# Shift_Registers.net
KiCad netlist of a schematic drawn in Altium Designer
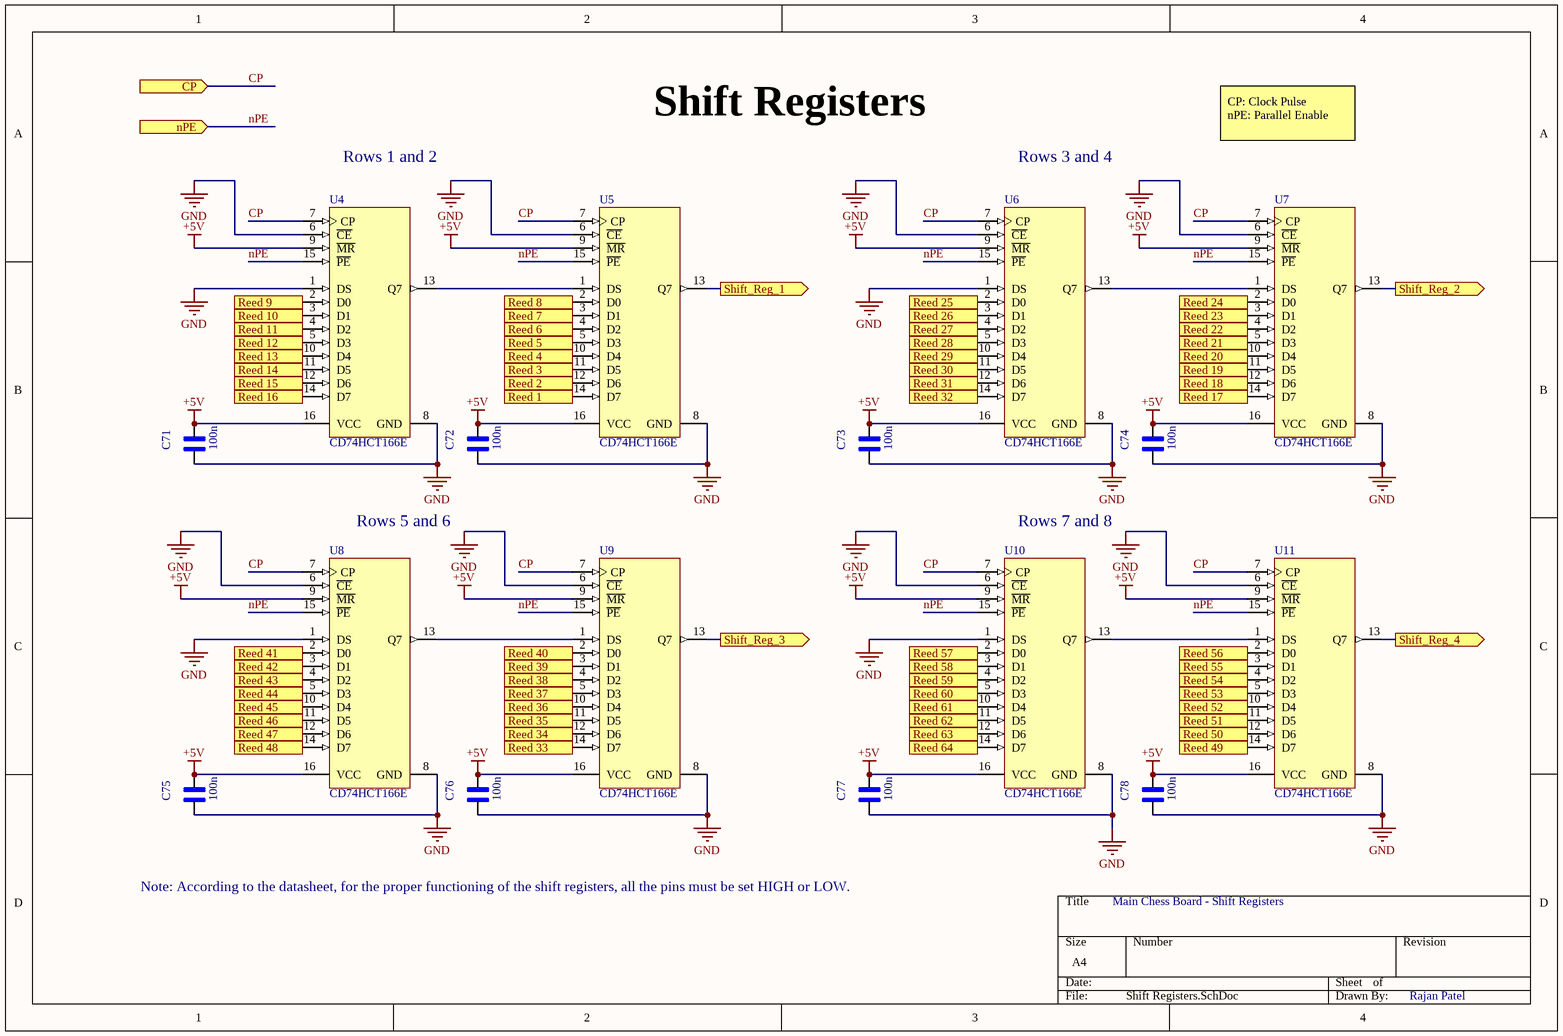
[diagram p0: Shift Registers.SchDoc]

(export (version "E")
  (design (tool "Eeschema 10.0.6"))
  (components
    (comp (ref "C71")
      (value "100n")
      (footprint "CAP 0805")
      (libsource (lib "MiniChessBoardSchLib") (part "CAP 0805"))
    )
    (comp (ref "C72")
      (value "100n")
      (footprint "CAP 0805")
      (libsource (lib "MiniChessBoardSchLib") (part "CAP 0805"))
    )
    (comp (ref "C73")
      (value "100n")
      (footprint "CAP 0805")
      (libsource (lib "MiniChessBoardSchLib") (part "CAP 0805"))
    )
    (comp (ref "C74")
      (value "100n")
      (footprint "CAP 0805")
      (libsource (lib "MiniChessBoardSchLib") (part "CAP 0805"))
    )
    (comp (ref "C75")
      (value "100n")
      (footprint "CAP 0805")
      (libsource (lib "MiniChessBoardSchLib") (part "CAP 0805"))
    )
    (comp (ref "C76")
      (value "100n")
      (footprint "CAP 0805")
      (libsource (lib "MiniChessBoardSchLib") (part "CAP 0805"))
    )
    (comp (ref "C77")
      (value "100n")
      (footprint "CAP 0805")
      (libsource (lib "MiniChessBoardSchLib") (part "CAP 0805"))
    )
    (comp (ref "C78")
      (value "100n")
      (footprint "CAP 0805")
      (libsource (lib "MiniChessBoardSchLib") (part "CAP 0805"))
    )
    (comp (ref "U4")
      (value "CD74HCT166E")
      (footprint "N0016A")
      (description "High Speed CMOS Logic 8-Bit Parallel-In/Serial-Out Shift Register, N0016A, TUBE")
      (fields
        (field (name "MANUFACTURER") "Texas Instruments")
        (field (name "GENERIC PART NUMBER") "CD74HCT166")
      )
      (libsource (lib "Altium Content Vault") (part "TI-CDX4HCX166-16"))
    )
    (comp (ref "U5")
      (value "CD74HCT166E")
      (footprint "N0016A")
      (description "High Speed CMOS Logic 8-Bit Parallel-In/Serial-Out Shift Register, N0016A, TUBE")
      (fields
        (field (name "MANUFACTURER") "Texas Instruments")
        (field (name "GENERIC PART NUMBER") "CD74HCT166")
      )
      (libsource (lib "Altium Content Vault") (part "TI-CDX4HCX166-16"))
    )
    (comp (ref "U6")
      (value "CD74HCT166E")
      (footprint "N0016A")
      (description "High Speed CMOS Logic 8-Bit Parallel-In/Serial-Out Shift Register, N0016A, TUBE")
      (fields
        (field (name "MANUFACTURER") "Texas Instruments")
        (field (name "GENERIC PART NUMBER") "CD74HCT166")
      )
      (libsource (lib "Altium Content Vault") (part "TI-CDX4HCX166-16"))
    )
    (comp (ref "U7")
      (value "CD74HCT166E")
      (footprint "N0016A")
      (description "High Speed CMOS Logic 8-Bit Parallel-In/Serial-Out Shift Register, N0016A, TUBE")
      (fields
        (field (name "MANUFACTURER") "Texas Instruments")
        (field (name "GENERIC PART NUMBER") "CD74HCT166")
      )
      (libsource (lib "Altium Content Vault") (part "TI-CDX4HCX166-16"))
    )
    (comp (ref "U8")
      (value "CD74HCT166E")
      (footprint "N0016A")
      (description "High Speed CMOS Logic 8-Bit Parallel-In/Serial-Out Shift Register, N0016A, TUBE")
      (fields
        (field (name "MANUFACTURER") "Texas Instruments")
        (field (name "GENERIC PART NUMBER") "CD74HCT166")
      )
      (libsource (lib "Altium Content Vault") (part "TI-CDX4HCX166-16"))
    )
    (comp (ref "U9")
      (value "CD74HCT166E")
      (footprint "N0016A")
      (description "High Speed CMOS Logic 8-Bit Parallel-In/Serial-Out Shift Register, N0016A, TUBE")
      (fields
        (field (name "MANUFACTURER") "Texas Instruments")
        (field (name "GENERIC PART NUMBER") "CD74HCT166")
      )
      (libsource (lib "Altium Content Vault") (part "TI-CDX4HCX166-16"))
    )
    (comp (ref "U10")
      (value "CD74HCT166E")
      (footprint "N0016A")
      (description "High Speed CMOS Logic 8-Bit Parallel-In/Serial-Out Shift Register, N0016A, TUBE")
      (fields
        (field (name "MANUFACTURER") "Texas Instruments")
        (field (name "GENERIC PART NUMBER") "CD74HCT166")
      )
      (libsource (lib "Altium Content Vault") (part "TI-CDX4HCX166-16"))
    )
    (comp (ref "U11")
      (value "CD74HCT166E")
      (footprint "N0016A")
      (description "High Speed CMOS Logic 8-Bit Parallel-In/Serial-Out Shift Register, N0016A, TUBE")
      (fields
        (field (name "MANUFACTURER") "Texas Instruments")
        (field (name "GENERIC PART NUMBER") "CD74HCT166")
      )
      (libsource (lib "Altium Content Vault") (part "TI-CDX4HCX166-16"))
    )
  )
  (nets
    (net (code "1") (name "+5V") (class "Default")
      (node (ref "C71") (pin "2") (pinfunction "2_2") (pintype "passive"))
      (node (ref "C72") (pin "2") (pinfunction "2_2") (pintype "passive"))
      (node (ref "C73") (pin "2") (pinfunction "2_2") (pintype "passive"))
      (node (ref "C74") (pin "2") (pinfunction "2_2") (pintype "passive"))
      (node (ref "C75") (pin "2") (pinfunction "2_2") (pintype "passive"))
      (node (ref "C76") (pin "2") (pinfunction "2_2") (pintype "passive"))
      (node (ref "C77") (pin "2") (pinfunction "2_2") (pintype "passive"))
      (node (ref "C78") (pin "2") (pinfunction "2_2") (pintype "passive"))
      (node (ref "U10") (pin "16") (pinfunction "VCC_16") (pintype "power_in"))
      (node (ref "U10") (pin "9") (pinfunction "~{MR}_9") (pintype "input"))
      (node (ref "U11") (pin "16") (pinfunction "VCC_16") (pintype "power_in"))
      (node (ref "U11") (pin "9") (pinfunction "~{MR}_9") (pintype "input"))
      (node (ref "U4") (pin "16") (pinfunction "VCC_16") (pintype "power_in"))
      (node (ref "U4") (pin "9") (pinfunction "~{MR}_9") (pintype "input"))
      (node (ref "U5") (pin "16") (pinfunction "VCC_16") (pintype "power_in"))
      (node (ref "U5") (pin "9") (pinfunction "~{MR}_9") (pintype "input"))
      (node (ref "U6") (pin "16") (pinfunction "VCC_16") (pintype "power_in"))
      (node (ref "U6") (pin "9") (pinfunction "~{MR}_9") (pintype "input"))
      (node (ref "U7") (pin "16") (pinfunction "VCC_16") (pintype "power_in"))
      (node (ref "U7") (pin "9") (pinfunction "~{MR}_9") (pintype "input"))
      (node (ref "U8") (pin "16") (pinfunction "VCC_16") (pintype "power_in"))
      (node (ref "U8") (pin "9") (pinfunction "~{MR}_9") (pintype "input"))
      (node (ref "U9") (pin "16") (pinfunction "VCC_16") (pintype "power_in"))
      (node (ref "U9") (pin "9") (pinfunction "~{MR}_9") (pintype "input"))
    )
    (net (code "2") (name "/CP") (class "Default")
      (node (ref "U10") (pin "7") (pinfunction "CP_7") (pintype "input"))
      (node (ref "U11") (pin "7") (pinfunction "CP_7") (pintype "input"))
      (node (ref "U4") (pin "7") (pinfunction "CP_7") (pintype "input"))
      (node (ref "U5") (pin "7") (pinfunction "CP_7") (pintype "input"))
      (node (ref "U6") (pin "7") (pinfunction "CP_7") (pintype "input"))
      (node (ref "U7") (pin "7") (pinfunction "CP_7") (pintype "input"))
      (node (ref "U8") (pin "7") (pinfunction "CP_7") (pintype "input"))
      (node (ref "U9") (pin "7") (pinfunction "CP_7") (pintype "input"))
    )
    (net (code "3") (name "/Reed 1") (class "Default")
      (node (ref "U5") (pin "14") (pinfunction "D7_14") (pintype "input"))
    )
    (net (code "4") (name "/Reed 2") (class "Default")
      (node (ref "U5") (pin "12") (pinfunction "D6_12") (pintype "input"))
    )
    (net (code "5") (name "/Reed 3") (class "Default")
      (node (ref "U5") (pin "11") (pinfunction "D5_11") (pintype "input"))
    )
    (net (code "6") (name "/Reed 4") (class "Default")
      (node (ref "U5") (pin "10") (pinfunction "D4_10") (pintype "input"))
    )
    (net (code "7") (name "/Reed 5") (class "Default")
      (node (ref "U5") (pin "5") (pinfunction "D3_5") (pintype "input"))
    )
    (net (code "8") (name "/Reed 6") (class "Default")
      (node (ref "U5") (pin "4") (pinfunction "D2_4") (pintype "input"))
    )
    (net (code "9") (name "/Reed 7") (class "Default")
      (node (ref "U5") (pin "3") (pinfunction "D1_3") (pintype "input"))
    )
    (net (code "10") (name "/Reed 8") (class "Default")
      (node (ref "U5") (pin "2") (pinfunction "D0_2") (pintype "input"))
    )
    (net (code "11") (name "/Reed 9") (class "Default")
      (node (ref "U4") (pin "2") (pinfunction "D0_2") (pintype "input"))
    )
    (net (code "12") (name "/Reed 10") (class "Default")
      (node (ref "U4") (pin "3") (pinfunction "D1_3") (pintype "input"))
    )
    (net (code "13") (name "/Reed 11") (class "Default")
      (node (ref "U4") (pin "4") (pinfunction "D2_4") (pintype "input"))
    )
    (net (code "14") (name "/Reed 12") (class "Default")
      (node (ref "U4") (pin "5") (pinfunction "D3_5") (pintype "input"))
    )
    (net (code "15") (name "/Reed 13") (class "Default")
      (node (ref "U4") (pin "10") (pinfunction "D4_10") (pintype "input"))
    )
    (net (code "16") (name "/Reed 14") (class "Default")
      (node (ref "U4") (pin "11") (pinfunction "D5_11") (pintype "input"))
    )
    (net (code "17") (name "/Reed 15") (class "Default")
      (node (ref "U4") (pin "12") (pinfunction "D6_12") (pintype "input"))
    )
    (net (code "18") (name "/Reed 16") (class "Default")
      (node (ref "U4") (pin "14") (pinfunction "D7_14") (pintype "input"))
    )
    (net (code "19") (name "/Reed 17") (class "Default")
      (node (ref "U7") (pin "14") (pinfunction "D7_14") (pintype "input"))
    )
    (net (code "20") (name "/Reed 18") (class "Default")
      (node (ref "U7") (pin "12") (pinfunction "D6_12") (pintype "input"))
    )
    (net (code "21") (name "/Reed 19") (class "Default")
      (node (ref "U7") (pin "11") (pinfunction "D5_11") (pintype "input"))
    )
    (net (code "22") (name "/Reed 20") (class "Default")
      (node (ref "U7") (pin "10") (pinfunction "D4_10") (pintype "input"))
    )
    (net (code "23") (name "/Reed 21") (class "Default")
      (node (ref "U7") (pin "5") (pinfunction "D3_5") (pintype "input"))
    )
    (net (code "24") (name "/Reed 22") (class "Default")
      (node (ref "U7") (pin "4") (pinfunction "D2_4") (pintype "input"))
    )
    (net (code "25") (name "/Reed 23") (class "Default")
      (node (ref "U7") (pin "3") (pinfunction "D1_3") (pintype "input"))
    )
    (net (code "26") (name "/Reed 24") (class "Default")
      (node (ref "U7") (pin "2") (pinfunction "D0_2") (pintype "input"))
    )
    (net (code "27") (name "/Reed 25") (class "Default")
      (node (ref "U6") (pin "2") (pinfunction "D0_2") (pintype "input"))
    )
    (net (code "28") (name "/Reed 26") (class "Default")
      (node (ref "U6") (pin "3") (pinfunction "D1_3") (pintype "input"))
    )
    (net (code "29") (name "/Reed 27") (class "Default")
      (node (ref "U6") (pin "4") (pinfunction "D2_4") (pintype "input"))
    )
    (net (code "30") (name "/Reed 28") (class "Default")
      (node (ref "U6") (pin "5") (pinfunction "D3_5") (pintype "input"))
    )
    (net (code "31") (name "/Reed 29") (class "Default")
      (node (ref "U6") (pin "10") (pinfunction "D4_10") (pintype "input"))
    )
    (net (code "32") (name "/Reed 30") (class "Default")
      (node (ref "U6") (pin "11") (pinfunction "D5_11") (pintype "input"))
    )
    (net (code "33") (name "/Reed 31") (class "Default")
      (node (ref "U6") (pin "12") (pinfunction "D6_12") (pintype "input"))
    )
    (net (code "34") (name "/Reed 32") (class "Default")
      (node (ref "U6") (pin "14") (pinfunction "D7_14") (pintype "input"))
    )
    (net (code "35") (name "/Reed 33") (class "Default")
      (node (ref "U9") (pin "14") (pinfunction "D7_14") (pintype "input"))
    )
    (net (code "36") (name "/Reed 34") (class "Default")
      (node (ref "U9") (pin "12") (pinfunction "D6_12") (pintype "input"))
    )
    (net (code "37") (name "/Reed 35") (class "Default")
      (node (ref "U9") (pin "11") (pinfunction "D5_11") (pintype "input"))
    )
    (net (code "38") (name "/Reed 36") (class "Default")
      (node (ref "U9") (pin "10") (pinfunction "D4_10") (pintype "input"))
    )
    (net (code "39") (name "/Reed 37") (class "Default")
      (node (ref "U9") (pin "5") (pinfunction "D3_5") (pintype "input"))
    )
    (net (code "40") (name "/Reed 38") (class "Default")
      (node (ref "U9") (pin "4") (pinfunction "D2_4") (pintype "input"))
    )
    (net (code "41") (name "/Reed 39") (class "Default")
      (node (ref "U9") (pin "3") (pinfunction "D1_3") (pintype "input"))
    )
    (net (code "42") (name "/Reed 40") (class "Default")
      (node (ref "U9") (pin "2") (pinfunction "D0_2") (pintype "input"))
    )
    (net (code "43") (name "/Reed 41") (class "Default")
      (node (ref "U8") (pin "2") (pinfunction "D0_2") (pintype "input"))
    )
    (net (code "44") (name "/Reed 42") (class "Default")
      (node (ref "U8") (pin "3") (pinfunction "D1_3") (pintype "input"))
    )
    (net (code "45") (name "/Reed 43") (class "Default")
      (node (ref "U8") (pin "4") (pinfunction "D2_4") (pintype "input"))
    )
    (net (code "46") (name "/Reed 44") (class "Default")
      (node (ref "U8") (pin "5") (pinfunction "D3_5") (pintype "input"))
    )
    (net (code "47") (name "/Reed 45") (class "Default")
      (node (ref "U8") (pin "10") (pinfunction "D4_10") (pintype "input"))
    )
    (net (code "48") (name "/Reed 46") (class "Default")
      (node (ref "U8") (pin "11") (pinfunction "D5_11") (pintype "input"))
    )
    (net (code "49") (name "/Reed 47") (class "Default")
      (node (ref "U8") (pin "12") (pinfunction "D6_12") (pintype "input"))
    )
    (net (code "50") (name "/Reed 48") (class "Default")
      (node (ref "U8") (pin "14") (pinfunction "D7_14") (pintype "input"))
    )
    (net (code "51") (name "/Reed 49") (class "Default")
      (node (ref "U11") (pin "14") (pinfunction "D7_14") (pintype "input"))
    )
    (net (code "52") (name "/Reed 50") (class "Default")
      (node (ref "U11") (pin "12") (pinfunction "D6_12") (pintype "input"))
    )
    (net (code "53") (name "/Reed 51") (class "Default")
      (node (ref "U11") (pin "11") (pinfunction "D5_11") (pintype "input"))
    )
    (net (code "54") (name "/Reed 52") (class "Default")
      (node (ref "U11") (pin "10") (pinfunction "D4_10") (pintype "input"))
    )
    (net (code "55") (name "/Reed 53") (class "Default")
      (node (ref "U11") (pin "5") (pinfunction "D3_5") (pintype "input"))
    )
    (net (code "56") (name "/Reed 54") (class "Default")
      (node (ref "U11") (pin "4") (pinfunction "D2_4") (pintype "input"))
    )
    (net (code "57") (name "/Reed 55") (class "Default")
      (node (ref "U11") (pin "3") (pinfunction "D1_3") (pintype "input"))
    )
    (net (code "58") (name "/Reed 56") (class "Default")
      (node (ref "U11") (pin "2") (pinfunction "D0_2") (pintype "input"))
    )
    (net (code "59") (name "/Reed 57") (class "Default")
      (node (ref "U10") (pin "2") (pinfunction "D0_2") (pintype "input"))
    )
    (net (code "60") (name "/Reed 58") (class "Default")
      (node (ref "U10") (pin "3") (pinfunction "D1_3") (pintype "input"))
    )
    (net (code "61") (name "/Reed 59") (class "Default")
      (node (ref "U10") (pin "4") (pinfunction "D2_4") (pintype "input"))
    )
    (net (code "62") (name "/Reed 60") (class "Default")
      (node (ref "U10") (pin "5") (pinfunction "D3_5") (pintype "input"))
    )
    (net (code "63") (name "/Reed 61") (class "Default")
      (node (ref "U10") (pin "10") (pinfunction "D4_10") (pintype "input"))
    )
    (net (code "64") (name "/Reed 62") (class "Default")
      (node (ref "U10") (pin "11") (pinfunction "D5_11") (pintype "input"))
    )
    (net (code "65") (name "/Reed 63") (class "Default")
      (node (ref "U10") (pin "12") (pinfunction "D6_12") (pintype "input"))
    )
    (net (code "66") (name "/Reed 64") (class "Default")
      (node (ref "U10") (pin "14") (pinfunction "D7_14") (pintype "input"))
    )
    (net (code "67") (name "/Shift_Reg_1") (class "Default")
      (node (ref "U5") (pin "13") (pinfunction "Q7_13") (pintype "output"))
    )
    (net (code "68") (name "/Shift_Reg_2") (class "Default")
      (node (ref "U7") (pin "13") (pinfunction "Q7_13") (pintype "output"))
    )
    (net (code "69") (name "/Shift_Reg_3") (class "Default")
      (node (ref "U9") (pin "13") (pinfunction "Q7_13") (pintype "output"))
    )
    (net (code "70") (name "/Shift_Reg_4") (class "Default")
      (node (ref "U11") (pin "13") (pinfunction "Q7_13") (pintype "output"))
    )
    (net (code "71") (name "/nPE") (class "Default")
      (node (ref "U10") (pin "15") (pinfunction "~{PE}_15") (pintype "input"))
      (node (ref "U11") (pin "15") (pinfunction "~{PE}_15") (pintype "input"))
      (node (ref "U4") (pin "15") (pinfunction "~{PE}_15") (pintype "input"))
      (node (ref "U5") (pin "15") (pinfunction "~{PE}_15") (pintype "input"))
      (node (ref "U6") (pin "15") (pinfunction "~{PE}_15") (pintype "input"))
      (node (ref "U7") (pin "15") (pinfunction "~{PE}_15") (pintype "input"))
      (node (ref "U8") (pin "15") (pinfunction "~{PE}_15") (pintype "input"))
      (node (ref "U9") (pin "15") (pinfunction "~{PE}_15") (pintype "input"))
    )
    (net (code "72") (name "GND") (class "Default")
      (node (ref "C71") (pin "1") (pinfunction "1_1") (pintype "passive"))
      (node (ref "C72") (pin "1") (pinfunction "1_1") (pintype "passive"))
      (node (ref "C73") (pin "1") (pinfunction "1_1") (pintype "passive"))
      (node (ref "C74") (pin "1") (pinfunction "1_1") (pintype "passive"))
      (node (ref "C75") (pin "1") (pinfunction "1_1") (pintype "passive"))
      (node (ref "C76") (pin "1") (pinfunction "1_1") (pintype "passive"))
      (node (ref "C77") (pin "1") (pinfunction "1_1") (pintype "passive"))
      (node (ref "C78") (pin "1") (pinfunction "1_1") (pintype "passive"))
      (node (ref "U10") (pin "1") (pinfunction "DS_1") (pintype "input"))
      (node (ref "U10") (pin "6") (pinfunction "~{CE}_6") (pintype "input"))
      (node (ref "U10") (pin "8") (pinfunction "GND_8") (pintype "power_in"))
      (node (ref "U11") (pin "6") (pinfunction "~{CE}_6") (pintype "input"))
      (node (ref "U11") (pin "8") (pinfunction "GND_8") (pintype "power_in"))
      (node (ref "U4") (pin "1") (pinfunction "DS_1") (pintype "input"))
      (node (ref "U4") (pin "6") (pinfunction "~{CE}_6") (pintype "input"))
      (node (ref "U4") (pin "8") (pinfunction "GND_8") (pintype "power_in"))
      (node (ref "U5") (pin "6") (pinfunction "~{CE}_6") (pintype "input"))
      (node (ref "U5") (pin "8") (pinfunction "GND_8") (pintype "power_in"))
      (node (ref "U6") (pin "1") (pinfunction "DS_1") (pintype "input"))
      (node (ref "U6") (pin "6") (pinfunction "~{CE}_6") (pintype "input"))
      (node (ref "U6") (pin "8") (pinfunction "GND_8") (pintype "power_in"))
      (node (ref "U7") (pin "6") (pinfunction "~{CE}_6") (pintype "input"))
      (node (ref "U7") (pin "8") (pinfunction "GND_8") (pintype "power_in"))
      (node (ref "U8") (pin "1") (pinfunction "DS_1") (pintype "input"))
      (node (ref "U8") (pin "6") (pinfunction "~{CE}_6") (pintype "input"))
      (node (ref "U8") (pin "8") (pinfunction "GND_8") (pintype "power_in"))
      (node (ref "U9") (pin "6") (pinfunction "~{CE}_6") (pintype "input"))
      (node (ref "U9") (pin "8") (pinfunction "GND_8") (pintype "power_in"))
    )
    (net (code "73") (name "Net-(U4-Q7)") (class "Default")
      (node (ref "U4") (pin "13") (pinfunction "Q7_13") (pintype "output"))
      (node (ref "U5") (pin "1") (pinfunction "DS_1") (pintype "input"))
    )
    (net (code "74") (name "Net-(U6-Q7)") (class "Default")
      (node (ref "U6") (pin "13") (pinfunction "Q7_13") (pintype "output"))
      (node (ref "U7") (pin "1") (pinfunction "DS_1") (pintype "input"))
    )
    (net (code "75") (name "Net-(U8-Q7)") (class "Default")
      (node (ref "U8") (pin "13") (pinfunction "Q7_13") (pintype "output"))
      (node (ref "U9") (pin "1") (pinfunction "DS_1") (pintype "input"))
    )
    (net (code "76") (name "Net-(U10-Q7)") (class "Default")
      (node (ref "U10") (pin "13") (pinfunction "Q7_13") (pintype "output"))
      (node (ref "U11") (pin "1") (pinfunction "DS_1") (pintype "input"))
    )
  )
)
